# turkin_ivt23_1d_list2.net
KiCad netlist of a schematic drawn in Altium Designer
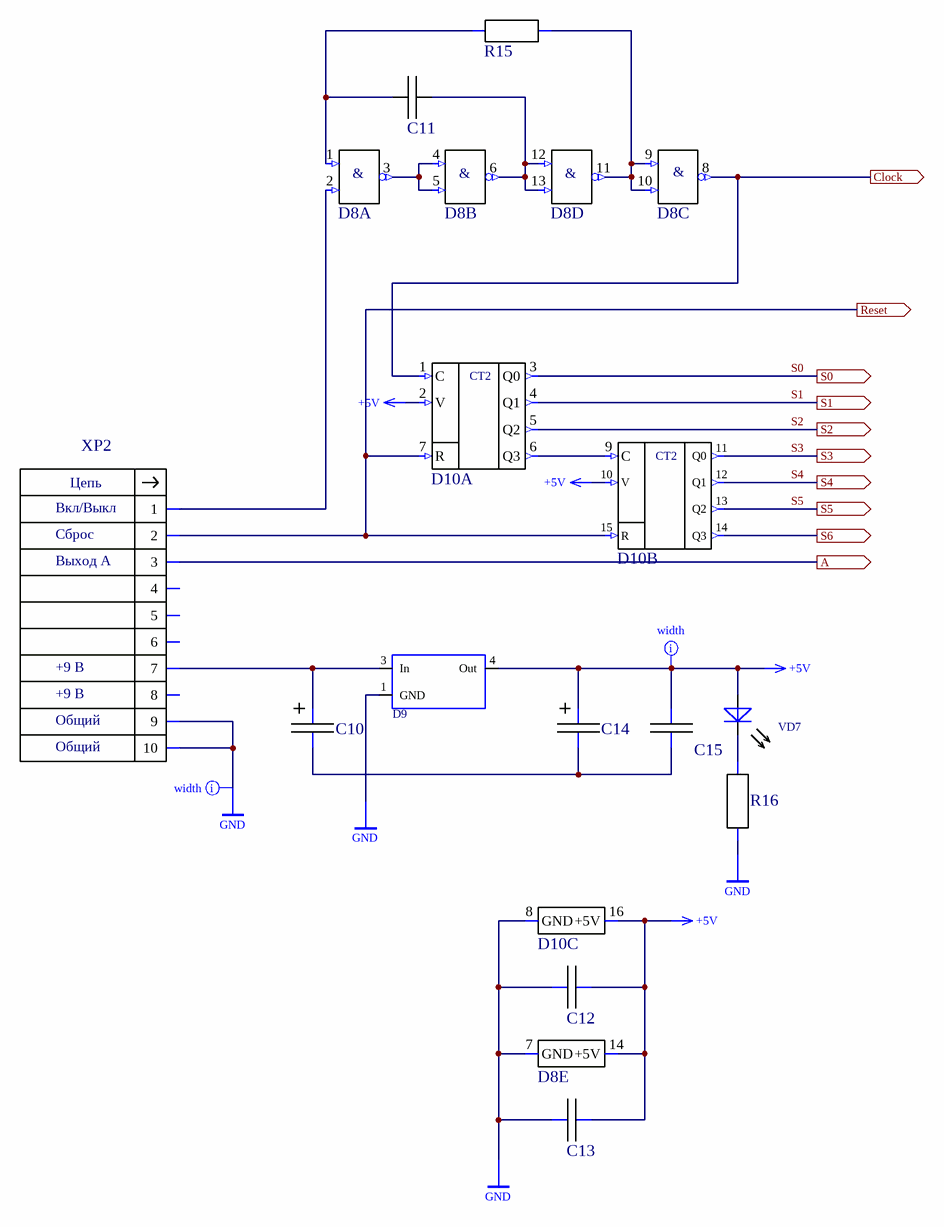
[diagram p0: turkin_ivt23_1d_list2.SchDoc]

(export (version "E")
  (design (tool "Eeschema 10.0.6"))
  (components
    (comp (ref "C10")
      (value "C")
      (footprint "C-Tantal")
      (description "К53-65 Конденсатор танталовый C(6032) 0,47-100 мкФ")
      (fields
        (field (name "VOLTAGE") "16В")
        (field (name "MANUFACTURER") "ОАО \"Элеконд\"")
        (field (name "CREATED_BY") "Желобаев")
      )
      (libsource (lib "Int_Library_for_Lessons_3") (part "K53-65_C_10%"))
    )
    (comp (ref "C11")
      (value "1210")
      (footprint "K10-79_3.2_2.5(1210)")
      (description "Чип конденсатор 1210 Н30 ряд Е6")
      (fields (field (name "MANUFACTURER") "ООО \"Кулон\"") (field (name "TOLERANCE") "±20%"))
      (libsource (lib "Int_Library_for_Lessons_3") (part "К10-79_1210_Н30"))
    )
    (comp (ref "C12")
      (value "~")
      (footprint "0805_N")
      (description "Чип конденсатор 0805 Н90 ряд Е6")
      (fields
        (field (name "MANUFACTURER") "ООО \"Кулон\"")
        (field (name "TOLERANCE") "+80%-20%")
        (field (name "CREATED_BY") "Желобаев")
      )
      (libsource (lib "Int_Library_for_Lessons_3") (part "К10-79_0805_Н90"))
    )
    (comp (ref "C13")
      (value "~")
      (footprint "0805_N")
      (description "Чип конденсатор 0805 Н90 ряд Е6")
      (fields
        (field (name "MANUFACTURER") "ООО \"Кулон\"")
        (field (name "TOLERANCE") "+80%-20%")
        (field (name "CREATED_BY") "Желобаев")
      )
      (libsource (lib "Int_Library_for_Lessons_3") (part "К10-79_0805_Н90"))
    )
    (comp (ref "C14")
      (value "C")
      (footprint "C-Tantal")
      (description "К53-65 Конденсатор танталовый C(6032) 0,47-100 мкФ")
      (fields
        (field (name "VOLTAGE") "16В")
        (field (name "MANUFACTURER") "ОАО \"Элеконд\"")
        (field (name "CREATED_BY") "Желобаев")
      )
      (libsource (lib "Int_Library_for_Lessons_3") (part "K53-65_C_10%"))
    )
    (comp (ref "C15")
      (value "~")
      (footprint "0805_N")
      (description "Чип конденсатор 0805 Н90 ряд Е6")
      (fields
        (field (name "MANUFACTURER") "ООО \"Кулон\"")
        (field (name "TOLERANCE") "+80%-20%")
        (field (name "CREATED_BY") "Желобаев")
      )
      (libsource (lib "Int_Library_for_Lessons_3") (part "К10-79_0805_Н90"))
    )
    (comp (ref "D8")
      (value "74AC00SC")
      (footprint "SO14-N")
      (description "4 элемента 2И-НЕ TTL SOIC-14")
      (fields (field (name "MANUFACTURER") "ON Semiconductor") (field (name "CREATED_BY") "Желобаев"))
      (libsource (lib "Int_Library_for_Lessons_3") (part "74AC00SC"))
    )
    (comp (ref "D9")
      (value "LM1117DTX-5.0/NOPB")
      (footprint "added_pcb:TO-252")
      (libsource (lib "added_elements") (part "LM1117DTX-5.0/NOPB"))
    )
    (comp (ref "D10")
      (value "~")
      (footprint "DIP16")
      (description "Два двоичных счетчика")
      (fields (field (name "MANUFACTURER") "Motorola") (field (name "CREATED_BY") "Желобаев"))
      (libsource (lib "Int_Library_for_Lessons_3") (part "MC14520BCP"))
    )
    (comp (ref "R15")
      (value "~")
      (footprint "RES_0603_1608_N")
      (description "Резистор от 0,75 Ом до 10 МОм")
      (fields
        (field (name "MANUFACTURER") "ОАО \"НПО \"Эркон\"")
        (field (name "TOLERANCE") "5%")
        (field (name "CREATED_BY") "Желобаев")
      )
      (libsource (lib "Int_Library_for_Lessons_3") (part "Р1-12-0,1-5%"))
    )
    (comp (ref "R16")
      (value "0805")
      (footprint "RES_0805_2012_N")
      (description "Резистор от 0,75 Ом до 2 МОм")
      (fields
        (field (name "MANUFACTURER") "ОАО \"НПО \"Эркон\"")
        (field (name "TOLERANCE") "5%")
        (field (name "CREATED_BY") "Желобаев")
      )
      (libsource (lib "Int_Library_for_Lessons_3") (part "Р1-12-0,125-5%"))
    )
    (comp (ref "VD7")
      (value "521-9466")
      (footprint "added_pcb:521-9466")
      (description "Светодиод 5мм желтый")
      (libsource (lib "added_elements") (part "521-9466"))
    )
    (comp (ref "XP2")
      (value "TE_1-1634689-0")
      (footprint "BH-10R")
      (description "Вилка типа BH-10R угловая правая двухрядная 2х5х2.54")
      (fields (field (name "MANUFACTURER") "TE Connectivity") (field (name "CREATED_BY") "Желобаев"))
      (libsource (lib "Int_Library_for_Lessons_3") (part "TE_1-1634689-0"))
    )
  )
  (nets
    (net (code "1") (name "+5V") (class "Default")
      (node (ref "C12") (pin "2") (pinfunction "2_2") (pintype "passive"))
      (node (ref "C13") (pin "2") (pinfunction "2_2") (pintype "passive"))
      (node (ref "C14") (pin "+") (pinfunction "+_+") (pintype "passive"))
      (node (ref "C15") (pin "1") (pinfunction "1_1") (pintype "passive"))
      (node (ref "D10") (pin "10") (pinfunction "V_10") (pintype "input"))
      (node (ref "D10") (pin "16") (pinfunction "+5V_16") (pintype "power_in"))
      (node (ref "D10") (pin "2") (pinfunction "V_2") (pintype "input"))
      (node (ref "D8") (pin "14") (pinfunction "+5V_14") (pintype "power_in"))
      (node (ref "D9") (pin "4") (pinfunction "Out_4") (pintype "power_in"))
      (node (ref "VD7") (pin "A") (pinfunction "A_A") (pintype "passive"))
    )
    (net (code "2") (name "/A") (class "Default")
      (node (ref "XP2") (pin "3") (pinfunction "3_3") (pintype "passive"))
    )
    (net (code "3") (name "/Clock") (class "Default")
      (node (ref "D10") (pin "1") (pinfunction "C_1") (pintype "input"))
      (node (ref "D8") (pin "8") (pinfunction "Out_8") (pintype "output"))
    )
    (net (code "4") (name "/Reset") (class "Default")
      (node (ref "D10") (pin "15") (pinfunction "R_15") (pintype "input"))
      (node (ref "D10") (pin "7") (pinfunction "R_7") (pintype "input"))
      (node (ref "XP2") (pin "2") (pinfunction "2_2") (pintype "passive"))
    )
    (net (code "5") (name "/S0") (class "Default")
      (node (ref "D10") (pin "3") (pinfunction "Q0_3") (pintype "output"))
    )
    (net (code "6") (name "/S1") (class "Default")
      (node (ref "D10") (pin "4") (pinfunction "Q1_4") (pintype "output"))
    )
    (net (code "7") (name "/S2") (class "Default")
      (node (ref "D10") (pin "5") (pinfunction "Q2_5") (pintype "output"))
    )
    (net (code "8") (name "/S3") (class "Default")
      (node (ref "D10") (pin "11") (pinfunction "Q0_11") (pintype "output"))
    )
    (net (code "9") (name "/S4") (class "Default")
      (node (ref "D10") (pin "12") (pinfunction "Q1_12") (pintype "output"))
    )
    (net (code "10") (name "/S5") (class "Default")
      (node (ref "D10") (pin "13") (pinfunction "Q2_13") (pintype "output"))
    )
    (net (code "11") (name "/S6") (class "Default")
      (node (ref "D10") (pin "14") (pinfunction "Q3_14") (pintype "output"))
    )
    (net (code "12") (name "GND") (class "Default")
      (node (ref "C12") (pin "1") (pinfunction "1_1") (pintype "passive"))
      (node (ref "C13") (pin "1") (pinfunction "1_1") (pintype "passive"))
      (node (ref "D10") (pin "8") (pinfunction "GND_8") (pintype "power_in"))
      (node (ref "D8") (pin "7") (pinfunction "GND_7") (pintype "power_in"))
      (node (ref "D9") (pin "1") (pinfunction "GND_1") (pintype "power_in"))
      (node (ref "R16") (pin "1") (pinfunction "1_1") (pintype "passive"))
      (node (ref "XP2") (pin "10") (pinfunction "10_10") (pintype "passive"))
      (node (ref "XP2") (pin "9") (pinfunction "9_9") (pintype "passive"))
    )
    (net (code "13") (name "Net-(C10-Pad-)") (class "Default")
      (node (ref "C10") (pin "-") (pinfunction "-_-") (pintype "passive"))
      (node (ref "C14") (pin "-") (pinfunction "-_-") (pintype "passive"))
      (node (ref "C15") (pin "2") (pinfunction "2_2") (pintype "passive"))
    )
    (net (code "14") (name "Net-(D8A-In1)") (class "Default")
      (node (ref "C11") (pin "1") (pinfunction "1_1") (pintype "passive"))
      (node (ref "D8") (pin "1") (pinfunction "In1_1") (pintype "input"))
      (node (ref "R15") (pin "1") (pinfunction "1_1") (pintype "passive"))
    )
    (net (code "15") (name "Net-(D8A-In2)") (class "Default")
      (node (ref "D8") (pin "2") (pinfunction "In2_2") (pintype "input"))
      (node (ref "XP2") (pin "1") (pinfunction "1_1") (pintype "passive"))
    )
    (net (code "16") (name "Net-(D8A-Out)") (class "Default")
      (node (ref "D8") (pin "3") (pinfunction "Out_3") (pintype "output"))
      (node (ref "D8") (pin "4") (pinfunction "In1_4") (pintype "input"))
      (node (ref "D8") (pin "5") (pinfunction "In2_5") (pintype "input"))
    )
    (net (code "17") (name "Net-(D8B-Out)") (class "Default")
      (node (ref "C11") (pin "2") (pinfunction "2_2") (pintype "passive"))
      (node (ref "D8") (pin "12") (pinfunction "In1_12") (pintype "input"))
      (node (ref "D8") (pin "13") (pinfunction "In2_13") (pintype "input"))
      (node (ref "D8") (pin "6") (pinfunction "Out_6") (pintype "output"))
    )
    (net (code "18") (name "Net-(D8C-In1)") (class "Default")
      (node (ref "D8") (pin "10") (pinfunction "In2_10") (pintype "input"))
      (node (ref "D8") (pin "11") (pinfunction "Out_11") (pintype "output"))
      (node (ref "D8") (pin "9") (pinfunction "In1_9") (pintype "input"))
      (node (ref "R15") (pin "2") (pinfunction "2_2") (pintype "passive"))
    )
    (net (code "19") (name "Net-(D9-In)") (class "Default")
      (node (ref "C10") (pin "+") (pinfunction "+_+") (pintype "passive"))
      (node (ref "D9") (pin "3") (pinfunction "In_3") (pintype "power_in"))
      (node (ref "XP2") (pin "7") (pinfunction "7_7") (pintype "passive"))
    )
    (net (code "20") (name "Net-(D10A-Q3)") (class "Default")
      (node (ref "D10") (pin "6") (pinfunction "Q3_6") (pintype "output"))
      (node (ref "D10") (pin "9") (pinfunction "C_9") (pintype "input"))
    )
    (net (code "21") (name "Net-(R16-Pad2)") (class "Default")
      (node (ref "R16") (pin "2") (pinfunction "2_2") (pintype "passive"))
      (node (ref "VD7") (pin "C") (pinfunction "C_C") (pintype "passive"))
    )
    (net (code "22") (name "unconnected-(XP2-Pad4)") (class "Default")
      (node (ref "XP2") (pin "4") (pinfunction "4_4") (pintype "passive"))
    )
    (net (code "23") (name "unconnected-(XP2-Pad5)") (class "Default")
      (node (ref "XP2") (pin "5") (pinfunction "5_5") (pintype "passive"))
    )
    (net (code "24") (name "unconnected-(XP2-Pad6)") (class "Default")
      (node (ref "XP2") (pin "6") (pinfunction "6_6") (pintype "passive"))
    )
    (net (code "25") (name "unconnected-(XP2-Pad8)") (class "Default")
      (node (ref "XP2") (pin "8") (pinfunction "8_8") (pintype "passive"))
    )
  )
)
